# Power.net
KiCad netlist of a schematic drawn in Altium Designer
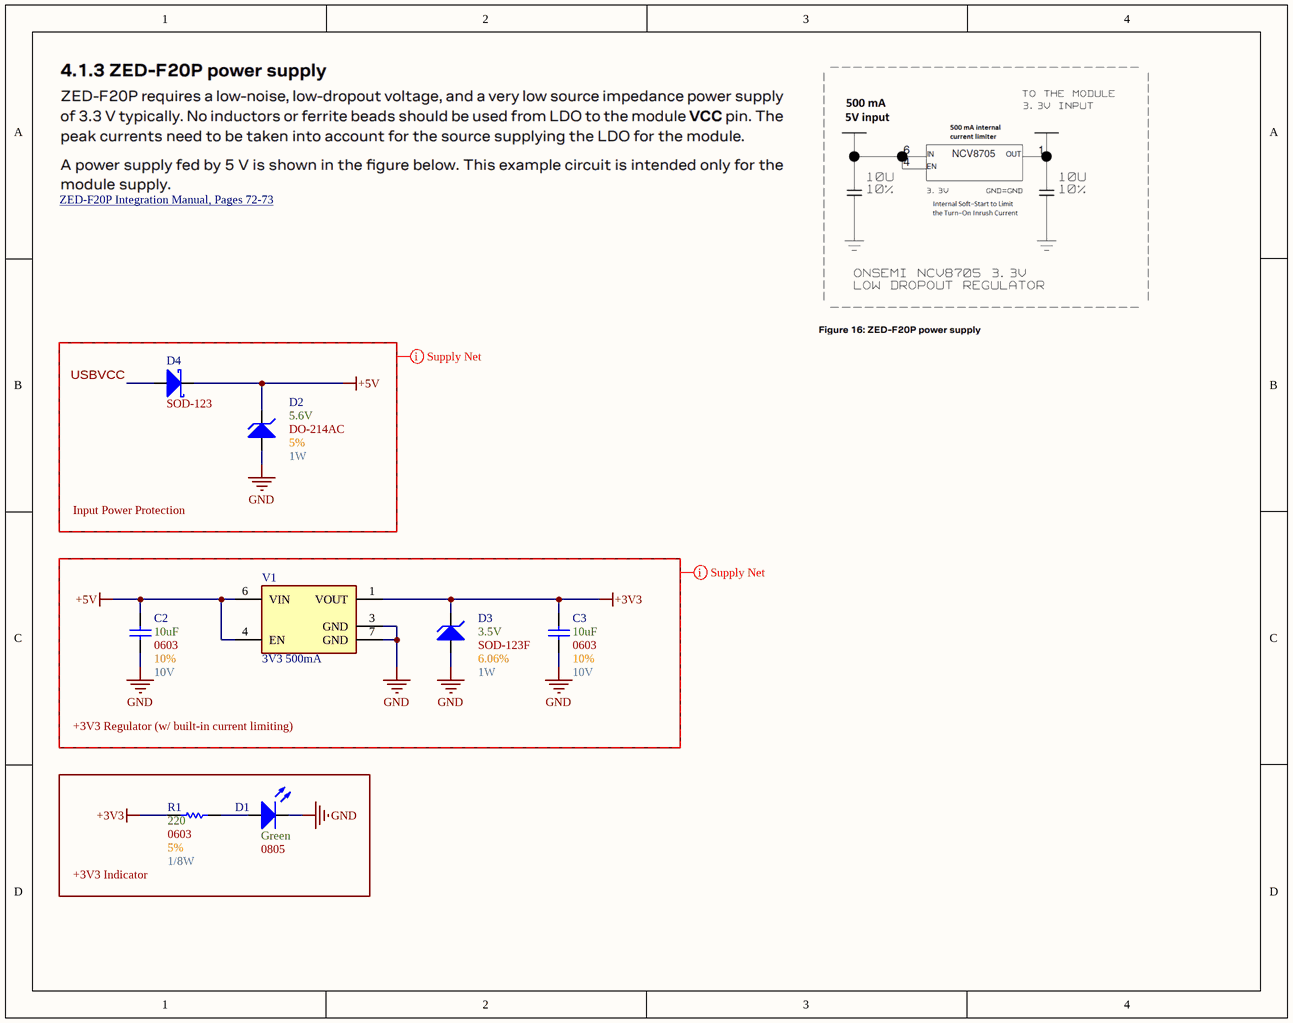
[diagram p0: Power.SchDoc]

(export (version "E")
  (design (tool "Eeschema 10.0.6"))
  (components
    (comp (ref "C2")
      (value "[Cap] 0603 10uF 10% 10V")
      (footprint "[Cap] SMD 0603")
      (description "CL10A106KP8NNNC")
      (fields
        (field (name "MAX VOLTAGE") "10V")
        (field (name "SIZE PACKAGE") "0603")
        (field (name "TOLERANCE") "10%")
        (field (name "CAPACITANCE") "10uF")
      )
      (libsource (lib "Capacitors") (part "[Cap] 0603 10uF 10% 10V"))
    )
    (comp (ref "C3")
      (value "[Cap] 0603 10uF 10% 10V")
      (footprint "[Cap] SMD 0603")
      (description "CL10A106KP8NNNC")
      (fields
        (field (name "MAX VOLTAGE") "10V")
        (field (name "SIZE PACKAGE") "0603")
        (field (name "TOLERANCE") "10%")
        (field (name "CAPACITANCE") "10uF")
      )
      (libsource (lib "Capacitors") (part "[Cap] 0603 10uF 10% 10V"))
    )
    (comp (ref "D1")
      (value "[LED] SMD 0805 Green")
      (footprint "[LED] SMD 0805")
      (description "LG R971-KN-1-0-20-R18")
      (fields (field (name "COLOR") "Green") (field (name "SIZE PACKAGE") "0805"))
      (libsource (lib "LEDs") (part "[LED] SMD 0805 Green"))
    )
    (comp (ref "D2")
      (value "DO-214AC")
      (footprint "DO-214AC")
      (description "SMAZ5V6-13-F")
      (fields
        (field (name "TOLERANCE") "5%")
        (field (name "WATTAGE") "1W")
        (field (name "OPTIMAL ZENER VOLTAGE") "5.6V")
      )
      (libsource (lib "Diodes") (part "[Zener] SMD 5.6V 1W 5%"))
    )
    (comp (ref "D3")
      (value "SOD-123F")
      (footprint "SOD-123F")
      (description "KDZVTR3.3B")
      (fields
        (field (name "TOLERANCE") "6.06%")
        (field (name "WATTAGE") "1W")
        (field (name "OPTIMAL ZENER VOLTAGE") "3.5V")
      )
      (libsource (lib "Diodes") (part "[Zener] SMD 3.5V 1W 6%"))
    )
    (comp (ref "D4")
      (value "SOD123")
      (footprint "SOD-123")
      (description "B5819W-TP")
      (libsource (lib "Diodes") (part "[Schottky] SMD 40V 1A"))
    )
    (comp (ref "R1")
      (value "[220] SMD 0603 5% 1/10W")
      (footprint "[Res] SMD 0603")
      (description "RK73B1JTTD221J")
      (fields
        (field (name "WATTAGE") "1/8W")
        (field (name "TOLERANCE") "5%")
        (field (name "RESISTANCE") "220")
        (field (name "SIZE PACKAGE") "0603")
      )
      (libsource (lib "Resistors") (part "[220] SMD 0603 5% 1/10W"))
    )
    (comp (ref "V1")
      (value "3V3 500mA")
      (footprint "[Linear] 3V3 0.5A")
      (description "NCV8705MT33TCG")
      (libsource (lib "Voltage Regulators") (part "[Linear] 3V3 0.5A"))
    )
  )
  (nets
    (net (code "1") (name "+3V3") (class "Default")
      (node (ref "C3") (pin "2") (pinfunction "2_2") (pintype "passive"))
      (node (ref "D3") (pin "1") (pinfunction "K_1") (pintype "passive"))
      (node (ref "R1") (pin "1") (pinfunction "1_1") (pintype "passive"))
      (node (ref "V1") (pin "1") (pinfunction "VOUT_1") (pintype "passive"))
    )
    (net (code "2") (name "+5V") (class "Default")
      (node (ref "C2") (pin "2") (pinfunction "2_2") (pintype "passive"))
      (node (ref "D2") (pin "1") (pinfunction "K_1") (pintype "passive"))
      (node (ref "D4") (pin "1") (pinfunction "K_1") (pintype "passive"))
      (node (ref "V1") (pin "4") (pinfunction "EN_4") (pintype "passive"))
      (node (ref "V1") (pin "6") (pinfunction "VIN_6") (pintype "passive"))
    )
    (net (code "3") (name "/USBVCC") (class "Default")
      (node (ref "D4") (pin "2") (pinfunction "A_2") (pintype "passive"))
    )
    (net (code "4") (name "GND") (class "Default")
      (node (ref "C2") (pin "1") (pinfunction "1_1") (pintype "passive"))
      (node (ref "C3") (pin "1") (pinfunction "1_1") (pintype "passive"))
      (node (ref "D1") (pin "2") (pinfunction "Cathode_2") (pintype "passive"))
      (node (ref "D2") (pin "2") (pinfunction "A_2") (pintype "passive"))
      (node (ref "D3") (pin "2") (pinfunction "A_2") (pintype "passive"))
      (node (ref "V1") (pin "3") (pinfunction "GND_3") (pintype "passive"))
      (node (ref "V1") (pin "7") (pinfunction "GND_7") (pintype "passive"))
    )
    (net (code "5") (name "Net-(D1-Anode)") (class "Default")
      (node (ref "D1") (pin "1") (pinfunction "Anode_1") (pintype "passive"))
      (node (ref "R1") (pin "2") (pinfunction "2_2") (pintype "passive"))
    )
  )
)
